# orient_test.net
KiCad netlist of a schematic drawn in EAGLE
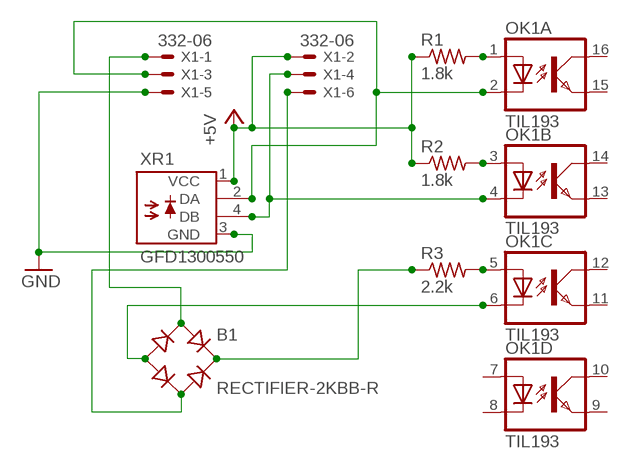
[diagram p0: schematic, sheet 1]

(export (version "E")
  (design (tool "Eeschema 10.0.6"))
  (components
    (comp (ref "B1")
      (value "RECTIFIER-2KBB-R")
      (footprint "eagle-import:2KBB-R")
      (libsource (lib "eagle-import") (part "RECTIFIER-2KBB-R"))
    )
    (comp (ref "OK1")
      (value "TIL193")
      (footprint "eagle-import:DIL16")
      (libsource (lib "eagle-import") (part "TIL193"))
    )
    (comp (ref "R1")
      (value "1.8k")
      (footprint "eagle-import:0204V")
      (libsource (lib "eagle-import") (part "R-US_0204/2V"))
    )
    (comp (ref "R2")
      (value "1.8k")
      (footprint "eagle-import:0204V")
      (libsource (lib "eagle-import") (part "R-US_0204/2V"))
    )
    (comp (ref "R3")
      (value "2.2k")
      (footprint "eagle-import:0204V")
      (libsource (lib "eagle-import") (part "R-US_0204/2V"))
    )
    (comp (ref "X1")
      (value "332-06")
      (footprint "eagle-import:332-06")
      (libsource (lib "eagle-import") (part "332-06"))
    )
    (comp (ref "XR1")
      (value "GFD1300550")
      (footprint "eagle-import:GFD1300")
      (libsource (lib "eagle-import") (part "GFD1300550"))
    )
  )
  (nets
    (net (code "1") (name "+5V") (class "Default")
      (node (ref "R1") (pin "1") (pinfunction "1_1") (pintype "passive"))
      (node (ref "R2") (pin "1") (pinfunction "1_1") (pintype "passive"))
      (node (ref "X1") (pin "2") (pinfunction "S_2") (pintype "passive"))
      (node (ref "XR1") (pin "1") (pinfunction "VCC_1") (pintype "power_in"))
    )
    (net (code "2") (name "GND") (class "Default")
      (node (ref "X1") (pin "5") (pinfunction "S_5") (pintype "passive"))
      (node (ref "XR1") (pin "3") (pinfunction "GND_3") (pintype "power_in"))
    )
    (net (code "3") (name "Net-(B1-Pad+)") (class "Default")
      (node (ref "B1") (pin "+") (pinfunction "+_+") (pintype "passive"))
      (node (ref "R3") (pin "1") (pinfunction "1_1") (pintype "passive"))
    )
    (net (code "4") (name "Net-(OK1A-A)") (class "Default")
      (node (ref "OK1") (pin "1") (pinfunction "A_1") (pintype "passive"))
      (node (ref "R1") (pin "2") (pinfunction "2_2") (pintype "passive"))
    )
    (net (code "5") (name "Net-(OK1A-C)") (class "Default")
      (node (ref "OK1") (pin "2") (pinfunction "C_2") (pintype "passive"))
      (node (ref "X1") (pin "3") (pinfunction "S_3") (pintype "passive"))
      (node (ref "XR1") (pin "2") (pinfunction "DA_2") (pintype "output"))
    )
    (net (code "6") (name "Net-(OK1B-A)") (class "Default")
      (node (ref "OK1") (pin "3") (pinfunction "A_3") (pintype "passive"))
      (node (ref "R2") (pin "2") (pinfunction "2_2") (pintype "passive"))
    )
    (net (code "7") (name "Net-(OK1B-C)") (class "Default")
      (node (ref "OK1") (pin "4") (pinfunction "C_4") (pintype "passive"))
      (node (ref "X1") (pin "4") (pinfunction "S_4") (pintype "passive"))
      (node (ref "XR1") (pin "4") (pinfunction "DB_4") (pintype "output"))
    )
    (net (code "8") (name "Net-(OK1C-A)") (class "Default")
      (node (ref "OK1") (pin "5") (pinfunction "A_5") (pintype "passive"))
      (node (ref "R3") (pin "2") (pinfunction "2_2") (pintype "passive"))
    )
    (net (code "9") (name "Net-(OK1C-C)") (class "Default")
      (node (ref "B1") (pin "-") (pinfunction "-_-") (pintype "passive"))
      (node (ref "OK1") (pin "6") (pinfunction "C_6") (pintype "passive"))
    )
    (net (code "10") (name "Net-(X1A-S)") (class "Default")
      (node (ref "B1") (pin "AC1") (pinfunction "AC1_AC1") (pintype "passive"))
      (node (ref "X1") (pin "1") (pinfunction "S_1") (pintype "passive"))
    )
    (net (code "11") (name "Net-(X1F-S)") (class "Default")
      (node (ref "B1") (pin "AC2") (pinfunction "AC2_AC2") (pintype "passive"))
      (node (ref "X1") (pin "6") (pinfunction "S_6") (pintype "passive"))
    )
    (net (code "12") (name "unconnected-(OK1A-COL-Pad16)") (class "Default")
      (node (ref "OK1") (pin "16") (pinfunction "COL_16") (pintype "passive"))
    )
    (net (code "13") (name "unconnected-(OK1A-EMIT-Pad15)") (class "Default")
      (node (ref "OK1") (pin "15") (pinfunction "EMIT_15") (pintype "passive"))
    )
    (net (code "14") (name "unconnected-(OK1B-COL-Pad14)") (class "Default")
      (node (ref "OK1") (pin "14") (pinfunction "COL_14") (pintype "passive"))
    )
    (net (code "15") (name "unconnected-(OK1B-EMIT-Pad13)") (class "Default")
      (node (ref "OK1") (pin "13") (pinfunction "EMIT_13") (pintype "passive"))
    )
    (net (code "16") (name "unconnected-(OK1C-COL-Pad12)") (class "Default")
      (node (ref "OK1") (pin "12") (pinfunction "COL_12") (pintype "passive"))
    )
    (net (code "17") (name "unconnected-(OK1C-EMIT-Pad11)") (class "Default")
      (node (ref "OK1") (pin "11") (pinfunction "EMIT_11") (pintype "passive"))
    )
    (net (code "18") (name "unconnected-(OK1D-A-Pad7)") (class "Default")
      (node (ref "OK1") (pin "7") (pinfunction "A_7") (pintype "passive"))
    )
    (net (code "19") (name "unconnected-(OK1D-C-Pad8)") (class "Default")
      (node (ref "OK1") (pin "8") (pinfunction "C_8") (pintype "passive"))
    )
    (net (code "20") (name "unconnected-(OK1D-COL-Pad10)") (class "Default")
      (node (ref "OK1") (pin "10") (pinfunction "COL_10") (pintype "passive"))
    )
    (net (code "21") (name "unconnected-(OK1D-EMIT-Pad9)") (class "Default")
      (node (ref "OK1") (pin "9") (pinfunction "EMIT_9") (pintype "passive"))
    )
  )
)
